# PCB_Tester1_V1_0.net
KiCad netlist of a schematic drawn in EAGLE
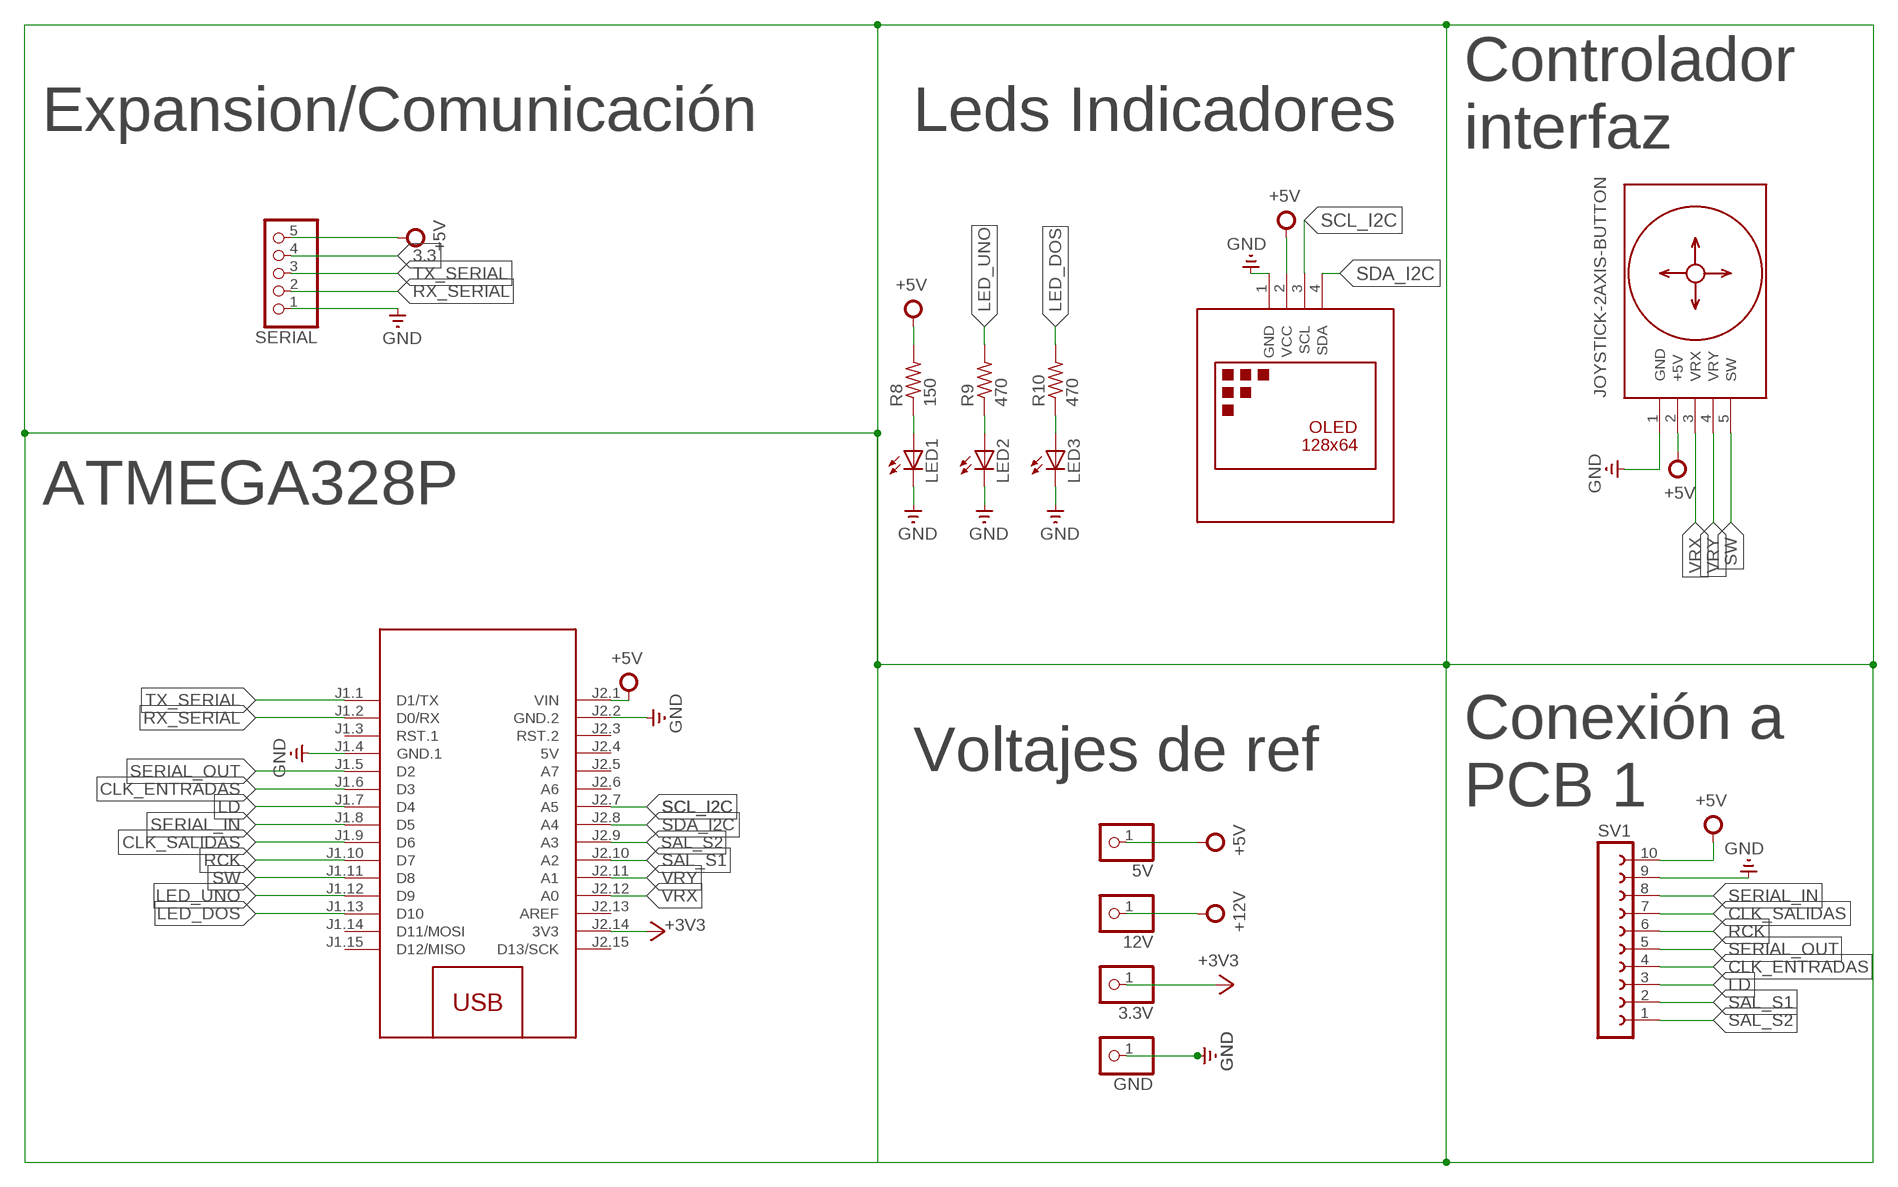
[diagram p0: schematic, sheet 1]

(export (version "E")
  (design (tool "Eeschema 10.0.6"))
  (components
    (comp (ref "3.3V")
      (value "PINHD-1X1")
      (footprint "eagle-import:1X01")
      (libsource (lib "eagle-import") (part "PINHD-1X1"))
    )
    (comp (ref "5V")
      (value "PINHD-1X1")
      (footprint "eagle-import:1X01")
      (libsource (lib "eagle-import") (part "PINHD-1X1"))
    )
    (comp (ref "12V")
      (value "PINHD-1X1")
      (footprint "eagle-import:1X01")
      (libsource (lib "eagle-import") (part "PINHD-1X1"))
    )
    (comp (ref "GND")
      (value "PINHD-1X1")
      (footprint "eagle-import:1X01")
      (libsource (lib "eagle-import") (part "PINHD-1X1"))
    )
    (comp (ref "LED1")
      (value "LED5MM")
      (footprint "eagle-import:LED5MM")
      (libsource (lib "eagle-import") (part "LED5MM"))
    )
    (comp (ref "LED2")
      (value "LED5MM")
      (footprint "eagle-import:LED5MM")
      (libsource (lib "eagle-import") (part "LED5MM"))
    )
    (comp (ref "LED3")
      (value "LED5MM")
      (footprint "eagle-import:LED5MM")
      (libsource (lib "eagle-import") (part "LED5MM"))
    )
    (comp (ref "M2")
      (value "ARDUINO-NANO-3.0")
      (footprint "eagle-import:ARDUINO-NANO-3.0")
      (libsource (lib "eagle-import") (part "ARDUINO-NANO-3.0"))
    )
    (comp (ref "R8")
      (value "150")
      (footprint "eagle-import:0207_7")
      (libsource (lib "eagle-import") (part "R-US_0207/7"))
    )
    (comp (ref "R9")
      (value "470")
      (footprint "eagle-import:0207_7")
      (libsource (lib "eagle-import") (part "R-US_0207/7"))
    )
    (comp (ref "R10")
      (value "470")
      (footprint "eagle-import:0207_7")
      (libsource (lib "eagle-import") (part "R-US_0207/7"))
    )
    (comp (ref "SERIAL")
      (value "PINHD-1X5")
      (footprint "eagle-import:1X05")
      (libsource (lib "eagle-import") (part "PINHD-1X5"))
    )
    (comp (ref "SV1")
      (value "FE10-1")
      (footprint "eagle-import:FE10")
      (libsource (lib "eagle-import") (part "FE10-1"))
    )
    (comp (ref "U$2")
      (value "DISPLAY-OLED-128X64-I2C")
      (footprint "eagle-import:DISPLAY-OLED-128X64-I2C")
      (libsource (lib "eagle-import") (part "DISPLAY-OLED-128X64-I2C"))
    )
    (comp (ref "U$3")
      (value "JOYSTICK-2AXIS-BUTTON")
      (footprint "eagle-import:JOYSTICK-2AXIS-BUTTON")
      (libsource (lib "eagle-import") (part "JOYSTICK-2AXIS-BUTTON"))
    )
  )
  (nets
    (net (code "1") (name "+3V3") (class "Default")
      (node (ref "3.3V") (pin "1") (pinfunction "1_1") (pintype "passive"))
      (node (ref "M2") (pin "J2.14") (pinfunction "3V3_J2.14") (pintype "power_in"))
    )
    (net (code "2") (name "+5V") (class "Default")
      (node (ref "5V") (pin "1") (pinfunction "1_1") (pintype "passive"))
      (node (ref "M2") (pin "J2.1") (pinfunction "VIN_J2.1") (pintype "power_in"))
      (node (ref "R8") (pin "2") (pinfunction "2_2") (pintype "passive"))
      (node (ref "SERIAL") (pin "5") (pinfunction "5_5") (pintype "passive"))
      (node (ref "SV1") (pin "10") (pinfunction "10_10") (pintype "passive"))
      (node (ref "U$2") (pin "2") (pinfunction "VCC_2") (pintype "power_in"))
      (node (ref "U$3") (pin "2") (pinfunction "+5V_2") (pintype "power_in"))
    )
    (net (code "3") (name "+12V") (class "Default")
      (node (ref "12V") (pin "1") (pinfunction "1_1") (pintype "passive"))
    )
    (net (code "4") (name "/5V") (class "Default")
      (node (ref "M2") (pin "J2.4") (pinfunction "5V_J2.4") (pintype "power_in"))
    )
    (net (code "5") (name "3.3") (class "Default")
      (node (ref "SERIAL") (pin "4") (pinfunction "4_4") (pintype "passive"))
    )
    (net (code "6") (name "CLK_ENTRADAS") (class "Default")
      (node (ref "M2") (pin "J1.6") (pinfunction "D3_J1.6") (pintype "bidirectional"))
      (node (ref "SV1") (pin "4") (pinfunction "4_4") (pintype "passive"))
    )
    (net (code "7") (name "CLK_SALIDAS") (class "Default")
      (node (ref "M2") (pin "J1.9") (pinfunction "D6_J1.9") (pintype "bidirectional"))
      (node (ref "SV1") (pin "7") (pinfunction "7_7") (pintype "passive"))
    )
    (net (code "8") (name "GND") (class "Default")
      (node (ref "GND") (pin "1") (pinfunction "1_1") (pintype "passive"))
      (node (ref "LED1") (pin "K") (pinfunction "C_K") (pintype "passive"))
      (node (ref "LED2") (pin "K") (pinfunction "C_K") (pintype "passive"))
      (node (ref "LED3") (pin "K") (pinfunction "C_K") (pintype "passive"))
      (node (ref "M2") (pin "J1.4") (pinfunction "GND.1_J1.4") (pintype "power_in"))
      (node (ref "M2") (pin "J2.2") (pinfunction "GND.2_J2.2") (pintype "power_in"))
      (node (ref "SERIAL") (pin "1") (pinfunction "1_1") (pintype "passive"))
      (node (ref "SV1") (pin "9") (pinfunction "9_9") (pintype "passive"))
      (node (ref "U$2") (pin "1") (pinfunction "GND_1") (pintype "power_in"))
      (node (ref "U$3") (pin "1") (pinfunction "GND_1") (pintype "power_in"))
    )
    (net (code "9") (name "LD") (class "Default")
      (node (ref "M2") (pin "J1.7") (pinfunction "D4_J1.7") (pintype "bidirectional"))
      (node (ref "SV1") (pin "3") (pinfunction "3_3") (pintype "passive"))
    )
    (net (code "10") (name "LED_DOS") (class "Default")
      (node (ref "M2") (pin "J1.13") (pinfunction "D10_J1.13") (pintype "bidirectional"))
      (node (ref "R10") (pin "2") (pinfunction "2_2") (pintype "passive"))
    )
    (net (code "11") (name "LED_UNO") (class "Default")
      (node (ref "M2") (pin "J1.12") (pinfunction "D9_J1.12") (pintype "bidirectional"))
      (node (ref "R9") (pin "2") (pinfunction "2_2") (pintype "passive"))
    )
    (net (code "12") (name "Net-(LED1-PadA)") (class "Default")
      (node (ref "LED1") (pin "A") (pinfunction "A_A") (pintype "passive"))
      (node (ref "R8") (pin "1") (pinfunction "1_1") (pintype "passive"))
    )
    (net (code "13") (name "Net-(LED2-PadA)") (class "Default")
      (node (ref "LED2") (pin "A") (pinfunction "A_A") (pintype "passive"))
      (node (ref "R9") (pin "1") (pinfunction "1_1") (pintype "passive"))
    )
    (net (code "14") (name "Net-(LED3-PadA)") (class "Default")
      (node (ref "LED3") (pin "A") (pinfunction "A_A") (pintype "passive"))
      (node (ref "R10") (pin "1") (pinfunction "1_1") (pintype "passive"))
    )
    (net (code "15") (name "RCK") (class "Default")
      (node (ref "M2") (pin "J1.10") (pinfunction "D7_J1.10") (pintype "bidirectional"))
      (node (ref "SV1") (pin "6") (pinfunction "6_6") (pintype "passive"))
    )
    (net (code "16") (name "RX_SERIAL") (class "Default")
      (node (ref "M2") (pin "J1.2") (pinfunction "D0/RX_J1.2") (pintype "bidirectional"))
      (node (ref "SERIAL") (pin "2") (pinfunction "2_2") (pintype "passive"))
    )
    (net (code "17") (name "SAL_S1") (class "Default")
      (node (ref "M2") (pin "J2.10") (pinfunction "A2_J2.10") (pintype "bidirectional"))
      (node (ref "SV1") (pin "2") (pinfunction "2_2") (pintype "passive"))
    )
    (net (code "18") (name "SAL_S2") (class "Default")
      (node (ref "M2") (pin "J2.9") (pinfunction "A3_J2.9") (pintype "bidirectional"))
      (node (ref "SV1") (pin "1") (pinfunction "1_1") (pintype "passive"))
    )
    (net (code "19") (name "SCL_I2C") (class "Default")
      (node (ref "M2") (pin "J2.7") (pinfunction "A5_J2.7") (pintype "bidirectional"))
      (node (ref "U$2") (pin "3") (pinfunction "SCL_3") (pintype "bidirectional"))
    )
    (net (code "20") (name "SDA_I2C") (class "Default")
      (node (ref "M2") (pin "J2.8") (pinfunction "A4_J2.8") (pintype "bidirectional"))
      (node (ref "U$2") (pin "4") (pinfunction "SDA_4") (pintype "bidirectional"))
    )
    (net (code "21") (name "SERIAL_IN") (class "Default")
      (node (ref "M2") (pin "J1.8") (pinfunction "D5_J1.8") (pintype "bidirectional"))
      (node (ref "SV1") (pin "8") (pinfunction "8_8") (pintype "passive"))
    )
    (net (code "22") (name "SERIAL_OUT") (class "Default")
      (node (ref "M2") (pin "J1.5") (pinfunction "D2_J1.5") (pintype "bidirectional"))
      (node (ref "SV1") (pin "5") (pinfunction "5_5") (pintype "passive"))
    )
    (net (code "23") (name "SW") (class "Default")
      (node (ref "M2") (pin "J1.11") (pinfunction "D8_J1.11") (pintype "bidirectional"))
      (node (ref "U$3") (pin "5") (pinfunction "SW_5") (pintype "passive"))
    )
    (net (code "24") (name "TX_SERIAL") (class "Default")
      (node (ref "M2") (pin "J1.1") (pinfunction "D1/TX_J1.1") (pintype "bidirectional"))
      (node (ref "SERIAL") (pin "3") (pinfunction "3_3") (pintype "passive"))
    )
    (net (code "25") (name "VRX") (class "Default")
      (node (ref "M2") (pin "J2.12") (pinfunction "A0_J2.12") (pintype "bidirectional"))
      (node (ref "U$3") (pin "3") (pinfunction "VRX_3") (pintype "passive"))
    )
    (net (code "26") (name "VRY") (class "Default")
      (node (ref "M2") (pin "J2.11") (pinfunction "A1_J2.11") (pintype "bidirectional"))
      (node (ref "U$3") (pin "4") (pinfunction "VRY_4") (pintype "passive"))
    )
    (net (code "27") (name "unconnected-(M2-A6-PadJ2.6)") (class "Default")
      (node (ref "M2") (pin "J2.6") (pinfunction "A6_J2.6") (pintype "bidirectional"))
    )
    (net (code "28") (name "unconnected-(M2-A7-PadJ2.5)") (class "Default")
      (node (ref "M2") (pin "J2.5") (pinfunction "A7_J2.5") (pintype "bidirectional"))
    )
    (net (code "29") (name "unconnected-(M2-AREF-PadJ2.13)") (class "Default")
      (node (ref "M2") (pin "J2.13") (pinfunction "AREF_J2.13") (pintype "bidirectional"))
    )
    (net (code "30") (name "unconnected-(M2-D11{slash}MOSI-PadJ1.14)") (class "Default")
      (node (ref "M2") (pin "J1.14") (pinfunction "D11/MOSI_J1.14") (pintype "bidirectional"))
    )
    (net (code "31") (name "unconnected-(M2-D12{slash}MISO-PadJ1.15)") (class "Default")
      (node (ref "M2") (pin "J1.15") (pinfunction "D12/MISO_J1.15") (pintype "bidirectional"))
    )
    (net (code "32") (name "unconnected-(M2-D13{slash}SCK-PadJ2.15)") (class "Default")
      (node (ref "M2") (pin "J2.15") (pinfunction "D13/SCK_J2.15") (pintype "bidirectional"))
    )
    (net (code "33") (name "unconnected-(M2-RST.1-PadJ1.3)") (class "Default")
      (node (ref "M2") (pin "J1.3") (pinfunction "RST.1_J1.3") (pintype "bidirectional"))
    )
    (net (code "34") (name "unconnected-(M2-RST.2-PadJ2.3)") (class "Default")
      (node (ref "M2") (pin "J2.3") (pinfunction "RST.2_J2.3") (pintype "bidirectional"))
    )
  )
)
